# badge_buttons.net
KiCad netlist of a schematic drawn in EAGLE
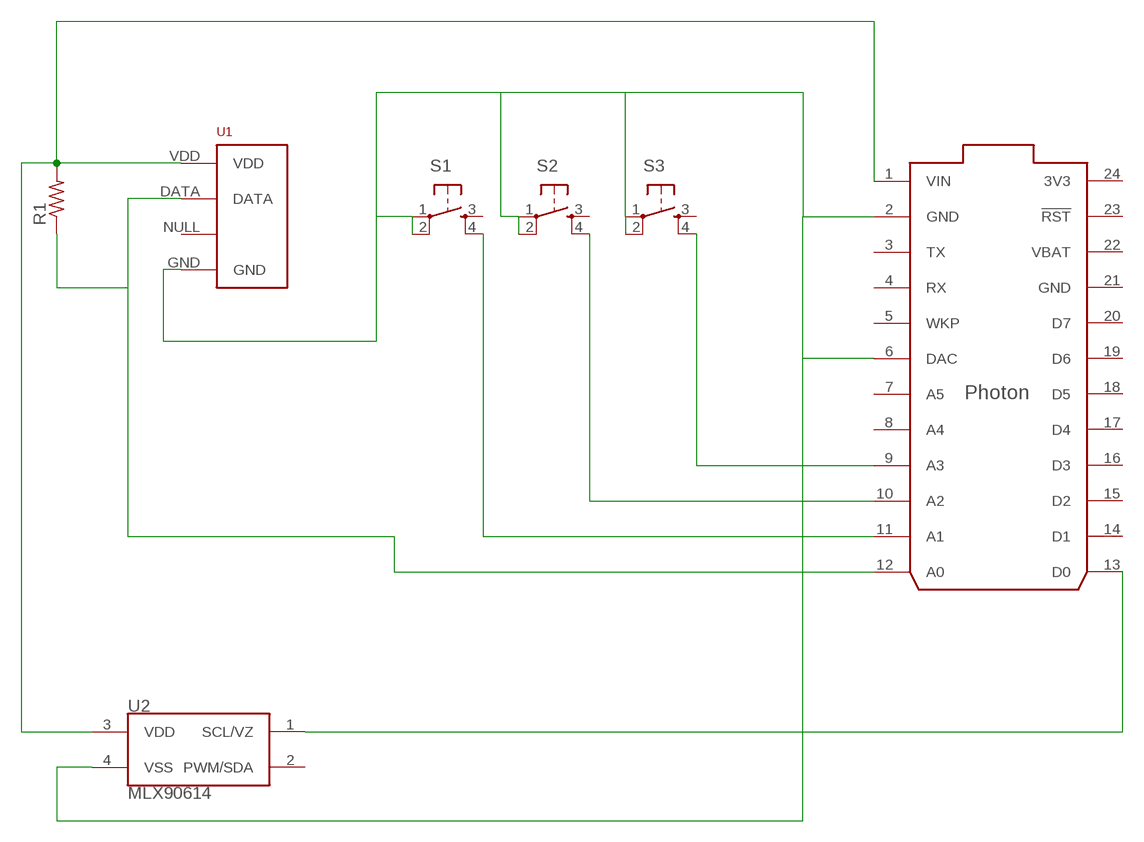
[diagram p0: schematic, sheet 1]

(export (version "E")
  (design (tool "Eeschema 10.0.6"))
  (components
    (comp (ref "R1")
      (value "R-US_0204/7")
      (footprint "eagle-import:0204_7")
      (libsource (lib "eagle-import") (part "R-US_0204/7"))
    )
    (comp (ref "S1")
      (value "TAC_SWITCHPTH")
      (footprint "eagle-import:TACTILE-PTH")
      (libsource (lib "eagle-import") (part "TAC_SWITCHPTH"))
    )
    (comp (ref "S2")
      (value "TAC_SWITCHPTH")
      (footprint "eagle-import:TACTILE-PTH")
      (libsource (lib "eagle-import") (part "TAC_SWITCHPTH"))
    )
    (comp (ref "S3")
      (value "TAC_SWITCHPTH")
      (footprint "eagle-import:TACTILE-PTH")
      (libsource (lib "eagle-import") (part "TAC_SWITCHPTH"))
    )
    (comp (ref "U$1")
      (value "PHOTON_WITH_HEADERS")
      (footprint "eagle-import:PHOTON")
      (libsource (lib "eagle-import") (part "PHOTON_WITH_HEADERS"))
    )
    (comp (ref "U1")
      (value "RHT03_DHT-22_AM2302")
      (footprint "eagle-import:RHT03_DHT-22")
      (libsource (lib "eagle-import") (part "RHT03_DHT-22_AM2302"))
    )
    (comp (ref "U2")
      (value "MLX90614")
      (footprint "eagle-import:TO-39")
      (libsource (lib "eagle-import") (part "MLX90614"))
    )
  )
  (nets
    (net (code "1") (name "/3V3") (class "Default")
      (node (ref "U$1") (pin "24") (pinfunction "3V3_24") (pintype "power_in"))
    )
    (net (code "2") (name "/GND") (class "Default")
      (node (ref "U$1") (pin "21") (pinfunction "GND_21") (pintype "power_in"))
    )
    (net (code "3") (name "/VBAT") (class "Default")
      (node (ref "U$1") (pin "22") (pinfunction "VBAT_22") (pintype "power_in"))
    )
    (net (code "4") (name "Net-(U$1-A0)") (class "Default")
      (node (ref "R1") (pin "1") (pinfunction "1_1") (pintype "passive"))
      (node (ref "U$1") (pin "12") (pinfunction "A0_12") (pintype "bidirectional"))
      (node (ref "U1") (pin "DATA") (pinfunction "DATA_DATA") (pintype "bidirectional"))
    )
    (net (code "5") (name "Net-(U$1-A1)") (class "Default")
      (node (ref "S1") (pin "4") (pinfunction "4_4") (pintype "passive"))
      (node (ref "U$1") (pin "11") (pinfunction "A1_11") (pintype "bidirectional"))
    )
    (net (code "6") (name "Net-(U$1-A2)") (class "Default")
      (node (ref "S2") (pin "4") (pinfunction "4_4") (pintype "passive"))
      (node (ref "U$1") (pin "10") (pinfunction "A2_10") (pintype "bidirectional"))
    )
    (net (code "7") (name "Net-(U$1-A3)") (class "Default")
      (node (ref "S3") (pin "4") (pinfunction "4_4") (pintype "passive"))
      (node (ref "U$1") (pin "9") (pinfunction "A3_9") (pintype "bidirectional"))
    )
    (net (code "8") (name "Net-(U$1-D0)") (class "Default")
      (node (ref "U$1") (pin "13") (pinfunction "D0_13") (pintype "bidirectional"))
      (node (ref "U2") (pin "1") (pinfunction "SCL/VZ_1") (pintype "bidirectional"))
    )
    (net (code "9") (name "Net-(U$1-DAC)") (class "Default")
      (node (ref "S1") (pin "1") (pinfunction "1_1") (pintype "passive"))
      (node (ref "S1") (pin "2") (pinfunction "2_2") (pintype "passive"))
      (node (ref "S2") (pin "1") (pinfunction "1_1") (pintype "passive"))
      (node (ref "S2") (pin "2") (pinfunction "2_2") (pintype "passive"))
      (node (ref "S3") (pin "1") (pinfunction "1_1") (pintype "passive"))
      (node (ref "S3") (pin "2") (pinfunction "2_2") (pintype "passive"))
      (node (ref "U$1") (pin "2") (pinfunction "GND_2") (pintype "power_in"))
      (node (ref "U$1") (pin "6") (pinfunction "DAC_6") (pintype "bidirectional"))
      (node (ref "U1") (pin "GND") (pinfunction "GND_GND") (pintype "power_in"))
      (node (ref "U2") (pin "4") (pinfunction "VSS_4") (pintype "bidirectional"))
    )
    (net (code "10") (name "Net-(U$1-VIN)") (class "Default")
      (node (ref "R1") (pin "2") (pinfunction "2_2") (pintype "passive"))
      (node (ref "U$1") (pin "1") (pinfunction "VIN_1") (pintype "power_in"))
      (node (ref "U1") (pin "VDD") (pinfunction "VDD_VDD") (pintype "power_in"))
      (node (ref "U2") (pin "3") (pinfunction "VDD_3") (pintype "bidirectional"))
    )
    (net (code "11") (name "unconnected-(S1-Pad3)") (class "Default")
      (node (ref "S1") (pin "3") (pinfunction "3_3") (pintype "passive"))
    )
    (net (code "12") (name "unconnected-(S2-Pad3)") (class "Default")
      (node (ref "S2") (pin "3") (pinfunction "3_3") (pintype "passive"))
    )
    (net (code "13") (name "unconnected-(S3-Pad3)") (class "Default")
      (node (ref "S3") (pin "3") (pinfunction "3_3") (pintype "passive"))
    )
    (net (code "14") (name "unconnected-(U$1-A4-Pad8)") (class "Default")
      (node (ref "U$1") (pin "8") (pinfunction "A4_8") (pintype "bidirectional"))
    )
    (net (code "15") (name "unconnected-(U$1-A5-Pad7)") (class "Default")
      (node (ref "U$1") (pin "7") (pinfunction "A5_7") (pintype "bidirectional"))
    )
    (net (code "16") (name "unconnected-(U$1-D1-Pad14)") (class "Default")
      (node (ref "U$1") (pin "14") (pinfunction "D1_14") (pintype "bidirectional"))
    )
    (net (code "17") (name "unconnected-(U$1-D2-Pad15)") (class "Default")
      (node (ref "U$1") (pin "15") (pinfunction "D2_15") (pintype "bidirectional"))
    )
    (net (code "18") (name "unconnected-(U$1-D3-Pad16)") (class "Default")
      (node (ref "U$1") (pin "16") (pinfunction "D3_16") (pintype "bidirectional"))
    )
    (net (code "19") (name "unconnected-(U$1-D4-Pad17)") (class "Default")
      (node (ref "U$1") (pin "17") (pinfunction "D4_17") (pintype "bidirectional"))
    )
    (net (code "20") (name "unconnected-(U$1-D5-Pad18)") (class "Default")
      (node (ref "U$1") (pin "18") (pinfunction "D5_18") (pintype "bidirectional"))
    )
    (net (code "21") (name "unconnected-(U$1-D6-Pad19)") (class "Default")
      (node (ref "U$1") (pin "19") (pinfunction "D6_19") (pintype "bidirectional"))
    )
    (net (code "22") (name "unconnected-(U$1-D7-Pad20)") (class "Default")
      (node (ref "U$1") (pin "20") (pinfunction "D7_20") (pintype "bidirectional"))
    )
    (net (code "23") (name "unconnected-(U$1-RX-Pad4)") (class "Default")
      (node (ref "U$1") (pin "4") (pinfunction "RX_4") (pintype "bidirectional"))
    )
    (net (code "24") (name "unconnected-(U$1-TX-Pad3)") (class "Default")
      (node (ref "U$1") (pin "3") (pinfunction "TX_3") (pintype "bidirectional"))
    )
    (net (code "25") (name "unconnected-(U$1-WKP-Pad5)") (class "Default")
      (node (ref "U$1") (pin "5") (pinfunction "WKP_5") (pintype "bidirectional"))
    )
    (net (code "26") (name "unconnected-(U$1-~{RST}-Pad23)") (class "Default")
      (node (ref "U$1") (pin "23") (pinfunction "~{RST}_23") (pintype "bidirectional"))
    )
    (net (code "27") (name "unconnected-(U1-PadNULL)") (class "Default")
      (node (ref "U1") (pin "NULL") (pinfunction "NULL_NULL") (pintype "no_connect"))
    )
    (net (code "28") (name "unconnected-(U2-PWM{slash}SDA-Pad2)") (class "Default")
      (node (ref "U2") (pin "2") (pinfunction "PWM/SDA_2") (pintype "bidirectional"))
    )
  )
)
